# Button_Board.net
KiCad netlist of a schematic drawn in Altium Designer
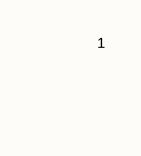
[diagram p0: Button Board.SchDoc, top right]
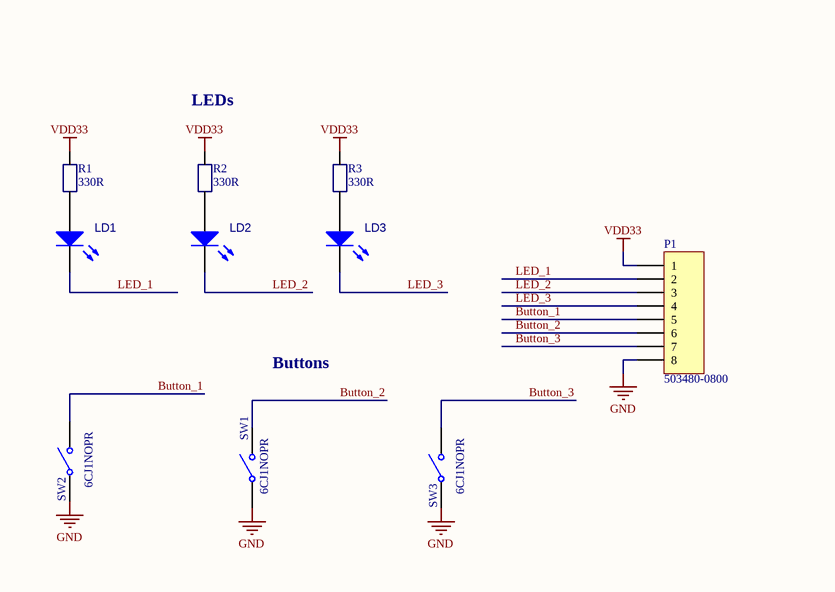
[diagram p1: Button Board.SchDoc, bottom left]

(export (version "E")
  (design (tool "Eeschema 10.0.6"))
  (components
    (comp (ref "LD1")
      (value "BLUE")
      (footprint "LEDC1608X80N_RED")
      (description "LED")
      (libsource (lib "GBX-ACW1.V1") (part "LED_GREEN_0603_THG1111C-0005-TR"))
    )
    (comp (ref "LD2")
      (value "BLUE")
      (footprint "LEDC1608X80N_RED")
      (description "LED")
      (libsource (lib "GBX-ACW1.V1") (part "LED_GREEN_0603_THG1111C-0005-TR"))
    )
    (comp (ref "LD3")
      (value "BLUE")
      (footprint "LEDC1608X80N_RED")
      (description "LED")
      (libsource (lib "GBX-ACW1.V1") (part "LED_GREEN_0603_THG1111C-0005-TR"))
    )
    (comp (ref "P1")
      (value "503480-0800")
      (footprint "503480-0800")
      (description "Header, 8-Pin")
      (fields (field (name "PUBLISHER") "Altium Limited"))
      (libsource (lib "Miscellaneous Connectors") (part "Header 8"))
    )
    (comp (ref "R1")
      (value "330R")
      (footprint "RESC1608X50N")
      (libsource (lib "Passive components") (part "Resistor"))
    )
    (comp (ref "R2")
      (value "330R")
      (footprint "RESC1608X50N")
      (libsource (lib "Passive components") (part "Resistor"))
    )
    (comp (ref "R3")
      (value "330R")
      (footprint "RESC1608X50N")
      (libsource (lib "Passive components") (part "Resistor"))
    )
    (comp (ref "SW1")
      (value "6CJ1NOPR")
      (footprint "Ultranavi_10G")
      (description "2.5mm 1.6mm Round Button 50mA Brick nogging 3mm SPST 12V SMD,2.5x3mm  Tactile Switches ROHS")
      (libsource (lib "Miscellaneous Devices") (part "SW-SPST"))
    )
    (comp (ref "SW2")
      (value "6CJ1NOPR")
      (footprint "Ultranavi_10S")
      (description "2.5mm 1.6mm Round Button 50mA Brick nogging 3mm SPST 12V SMD,2.5x3mm  Tactile Switches ROHS")
      (libsource (lib "Miscellaneous Devices") (part "SW-SPST"))
    )
    (comp (ref "SW3")
      (value "6CJ1NOPR")
      (footprint "Ultranavi_10S")
      (description "2.5mm 1.6mm Round Button 50mA Brick nogging 3mm SPST 12V SMD,2.5x3mm  Tactile Switches ROHS")
      (libsource (lib "Miscellaneous Devices") (part "SW-SPST"))
    )
  )
  (nets
    (net (code "1") (name "/Button_1") (class "Default")
      (node (ref "P1") (pin "5") (pinfunction "5_5") (pintype "passive"))
      (node (ref "SW2") (pin "2") (pinfunction "NO_2") (pintype "passive"))
    )
    (net (code "2") (name "/Button_2") (class "Default")
      (node (ref "P1") (pin "6") (pinfunction "6_6") (pintype "passive"))
      (node (ref "SW1") (pin "2") (pinfunction "NO_2") (pintype "passive"))
    )
    (net (code "3") (name "/Button_3") (class "Default")
      (node (ref "P1") (pin "7") (pinfunction "7_7") (pintype "passive"))
      (node (ref "SW3") (pin "2") (pinfunction "NO_2") (pintype "passive"))
    )
    (net (code "4") (name "/LED_1") (class "Default")
      (node (ref "LD1") (pin "2") (pinfunction "K_2") (pintype "passive"))
      (node (ref "P1") (pin "2") (pinfunction "2_2") (pintype "passive"))
    )
    (net (code "5") (name "/LED_2") (class "Default")
      (node (ref "LD2") (pin "2") (pinfunction "K_2") (pintype "passive"))
      (node (ref "P1") (pin "3") (pinfunction "3_3") (pintype "passive"))
    )
    (net (code "6") (name "/LED_3") (class "Default")
      (node (ref "LD3") (pin "2") (pinfunction "K_2") (pintype "passive"))
      (node (ref "P1") (pin "4") (pinfunction "4_4") (pintype "passive"))
    )
    (net (code "7") (name "GND") (class "Default")
      (node (ref "P1") (pin "8") (pinfunction "8_8") (pintype "passive"))
      (node (ref "SW1") (pin "1") (pinfunction "COMMON_1") (pintype "passive"))
      (node (ref "SW2") (pin "1") (pinfunction "COMMON_1") (pintype "passive"))
      (node (ref "SW3") (pin "1") (pinfunction "COMMON_1") (pintype "passive"))
    )
    (net (code "8") (name "Net-(LD1-A)") (class "Default")
      (node (ref "LD1") (pin "1") (pinfunction "A_1") (pintype "passive"))
      (node (ref "R1") (pin "1") (pinfunction "1_1") (pintype "passive"))
    )
    (net (code "9") (name "Net-(LD2-A)") (class "Default")
      (node (ref "LD2") (pin "1") (pinfunction "A_1") (pintype "passive"))
      (node (ref "R2") (pin "1") (pinfunction "1_1") (pintype "passive"))
    )
    (net (code "10") (name "Net-(LD3-A)") (class "Default")
      (node (ref "LD3") (pin "1") (pinfunction "A_1") (pintype "passive"))
      (node (ref "R3") (pin "1") (pinfunction "1_1") (pintype "passive"))
    )
    (net (code "11") (name "VDD33") (class "Default")
      (node (ref "P1") (pin "1") (pinfunction "1_1") (pintype "passive"))
      (node (ref "R1") (pin "2") (pinfunction "2_2") (pintype "passive"))
      (node (ref "R2") (pin "2") (pinfunction "2_2") (pintype "passive"))
      (node (ref "R3") (pin "2") (pinfunction "2_2") (pintype "passive"))
    )
  )
)
